# 28_main_board_vA.net
KiCad netlist of a schematic drawn in EAGLE
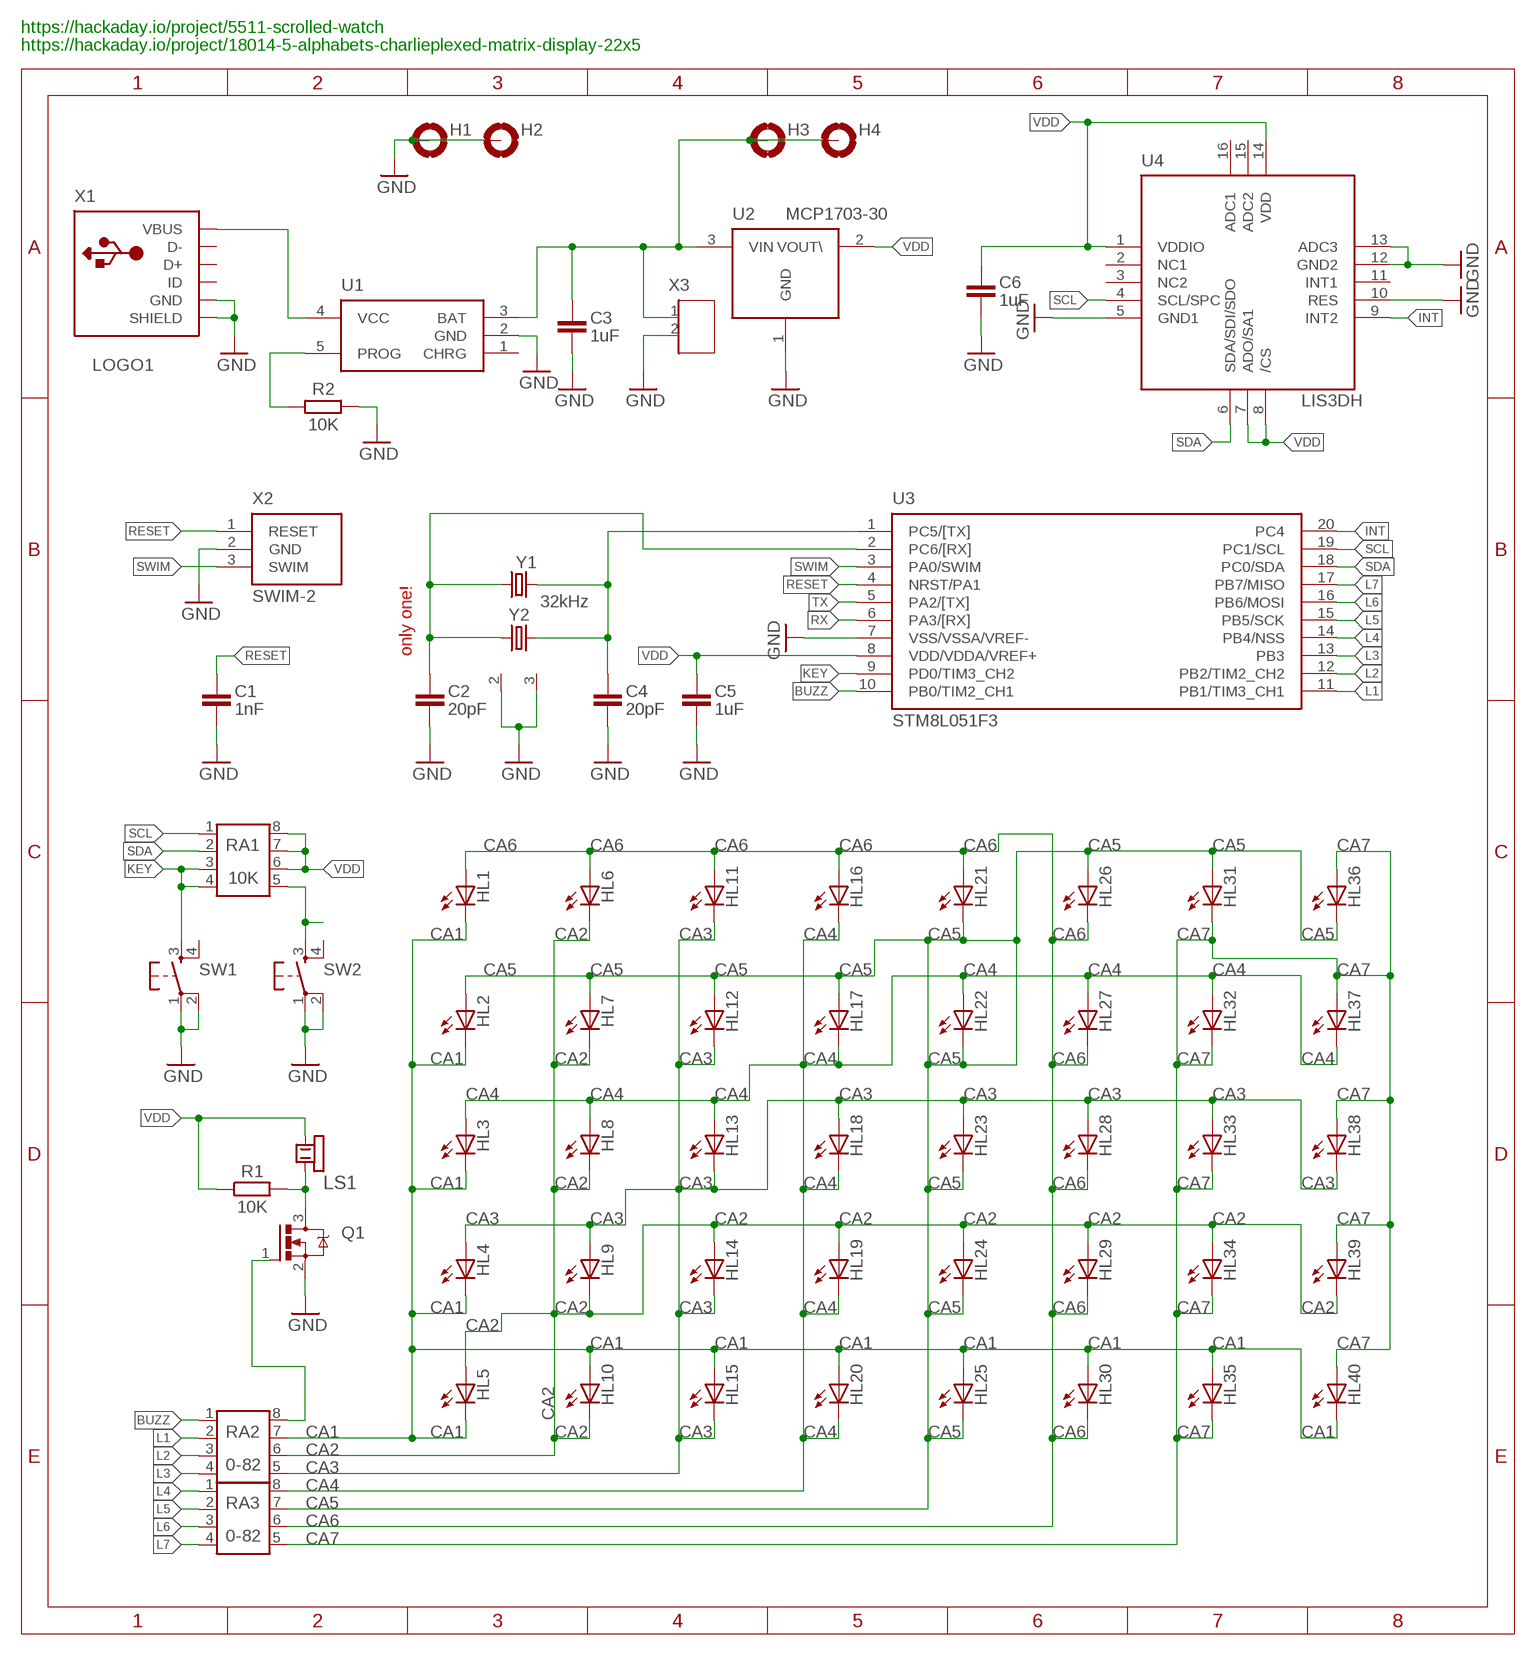
[diagram p0: schematic, sheet 1]

(export (version "E")
  (design (tool "Eeschema 10.0.6"))
  (components
    (comp (ref "C1")
      (value "1nF")
      (footprint "eagle-import:C0603")
      (libsource (lib "eagle-import") (part "C-EU-C0603"))
    )
    (comp (ref "C2")
      (value "20pF")
      (footprint "eagle-import:C0402")
      (libsource (lib "eagle-import") (part "C-EU-C0402"))
    )
    (comp (ref "C3")
      (value "1uF")
      (footprint "eagle-import:C0603")
      (libsource (lib "eagle-import") (part "C-EU-C0603"))
    )
    (comp (ref "C4")
      (value "20pF")
      (footprint "eagle-import:C0402")
      (libsource (lib "eagle-import") (part "C-EU-C0402"))
    )
    (comp (ref "C5")
      (value "1uF")
      (footprint "eagle-import:C0603")
      (libsource (lib "eagle-import") (part "C-EU-C0603"))
    )
    (comp (ref "C6")
      (value "1uF")
      (footprint "eagle-import:C0603")
      (libsource (lib "eagle-import") (part "C-EU-C0603"))
    )
    (comp (ref "H1")
      (value "MOUNT-PAD-ROUNDVA")
      (footprint "eagle-import:PAD-VA")
      (libsource (lib "eagle-import") (part "MOUNT-PAD-ROUNDVA"))
    )
    (comp (ref "H2")
      (value "MOUNT-PAD-ROUNDVA")
      (footprint "eagle-import:PAD-VA")
      (libsource (lib "eagle-import") (part "MOUNT-PAD-ROUNDVA"))
    )
    (comp (ref "H3")
      (value "MOUNT-PAD-ROUNDVA")
      (footprint "eagle-import:PAD-VA")
      (libsource (lib "eagle-import") (part "MOUNT-PAD-ROUNDVA"))
    )
    (comp (ref "H4")
      (value "MOUNT-PAD-ROUNDVA")
      (footprint "eagle-import:PAD-VA")
      (libsource (lib "eagle-import") (part "MOUNT-PAD-ROUNDVA"))
    )
    (comp (ref "HL1")
      (value "LED0603")
      (footprint "eagle-import:CHIPLED_0603")
      (libsource (lib "eagle-import") (part "LED0603"))
    )
    (comp (ref "HL2")
      (value "LED0603")
      (footprint "eagle-import:CHIPLED_0603")
      (libsource (lib "eagle-import") (part "LED0603"))
    )
    (comp (ref "HL3")
      (value "LED0603")
      (footprint "eagle-import:CHIPLED_0603")
      (libsource (lib "eagle-import") (part "LED0603"))
    )
    (comp (ref "HL4")
      (value "LED0603")
      (footprint "eagle-import:CHIPLED_0603")
      (libsource (lib "eagle-import") (part "LED0603"))
    )
    (comp (ref "HL5")
      (value "LED0603")
      (footprint "eagle-import:CHIPLED_0603")
      (libsource (lib "eagle-import") (part "LED0603"))
    )
    (comp (ref "HL6")
      (value "LED0603")
      (footprint "eagle-import:CHIPLED_0603")
      (libsource (lib "eagle-import") (part "LED0603"))
    )
    (comp (ref "HL7")
      (value "LED0603")
      (footprint "eagle-import:CHIPLED_0603")
      (libsource (lib "eagle-import") (part "LED0603"))
    )
    (comp (ref "HL8")
      (value "LED0603")
      (footprint "eagle-import:CHIPLED_0603")
      (libsource (lib "eagle-import") (part "LED0603"))
    )
    (comp (ref "HL9")
      (value "LED0603")
      (footprint "eagle-import:CHIPLED_0603")
      (libsource (lib "eagle-import") (part "LED0603"))
    )
    (comp (ref "HL10")
      (value "LED0603")
      (footprint "eagle-import:CHIPLED_0603")
      (libsource (lib "eagle-import") (part "LED0603"))
    )
    (comp (ref "HL11")
      (value "LED0603")
      (footprint "eagle-import:CHIPLED_0603")
      (libsource (lib "eagle-import") (part "LED0603"))
    )
    (comp (ref "HL12")
      (value "LED0603")
      (footprint "eagle-import:CHIPLED_0603")
      (libsource (lib "eagle-import") (part "LED0603"))
    )
    (comp (ref "HL13")
      (value "LED0603")
      (footprint "eagle-import:CHIPLED_0603")
      (libsource (lib "eagle-import") (part "LED0603"))
    )
    (comp (ref "HL14")
      (value "LED0603")
      (footprint "eagle-import:CHIPLED_0603")
      (libsource (lib "eagle-import") (part "LED0603"))
    )
    (comp (ref "HL15")
      (value "LED0603")
      (footprint "eagle-import:CHIPLED_0603")
      (libsource (lib "eagle-import") (part "LED0603"))
    )
    (comp (ref "HL16")
      (value "LED0603")
      (footprint "eagle-import:CHIPLED_0603")
      (libsource (lib "eagle-import") (part "LED0603"))
    )
    (comp (ref "HL17")
      (value "LED0603")
      (footprint "eagle-import:CHIPLED_0603")
      (libsource (lib "eagle-import") (part "LED0603"))
    )
    (comp (ref "HL18")
      (value "LED0603")
      (footprint "eagle-import:CHIPLED_0603")
      (libsource (lib "eagle-import") (part "LED0603"))
    )
    (comp (ref "HL19")
      (value "LED0603")
      (footprint "eagle-import:CHIPLED_0603")
      (libsource (lib "eagle-import") (part "LED0603"))
    )
    (comp (ref "HL20")
      (value "LED0603")
      (footprint "eagle-import:CHIPLED_0603")
      (libsource (lib "eagle-import") (part "LED0603"))
    )
    (comp (ref "HL21")
      (value "LED0603")
      (footprint "eagle-import:CHIPLED_0603")
      (libsource (lib "eagle-import") (part "LED0603"))
    )
    (comp (ref "HL22")
      (value "LED0603")
      (footprint "eagle-import:CHIPLED_0603")
      (libsource (lib "eagle-import") (part "LED0603"))
    )
    (comp (ref "HL23")
      (value "LED0603")
      (footprint "eagle-import:CHIPLED_0603")
      (libsource (lib "eagle-import") (part "LED0603"))
    )
    (comp (ref "HL24")
      (value "LED0603")
      (footprint "eagle-import:CHIPLED_0603")
      (libsource (lib "eagle-import") (part "LED0603"))
    )
    (comp (ref "HL25")
      (value "LED0603")
      (footprint "eagle-import:CHIPLED_0603")
      (libsource (lib "eagle-import") (part "LED0603"))
    )
    (comp (ref "HL26")
      (value "LED0603")
      (footprint "eagle-import:CHIPLED_0603")
      (libsource (lib "eagle-import") (part "LED0603"))
    )
    (comp (ref "HL27")
      (value "LED0603")
      (footprint "eagle-import:CHIPLED_0603")
      (libsource (lib "eagle-import") (part "LED0603"))
    )
    (comp (ref "HL28")
      (value "LED0603")
      (footprint "eagle-import:CHIPLED_0603")
      (libsource (lib "eagle-import") (part "LED0603"))
    )
    (comp (ref "HL29")
      (value "LED0603")
      (footprint "eagle-import:CHIPLED_0603")
      (libsource (lib "eagle-import") (part "LED0603"))
    )
    (comp (ref "HL30")
      (value "LED0603")
      (footprint "eagle-import:CHIPLED_0603")
      (libsource (lib "eagle-import") (part "LED0603"))
    )
    (comp (ref "HL31")
      (value "LED0603")
      (footprint "eagle-import:CHIPLED_0603")
      (libsource (lib "eagle-import") (part "LED0603"))
    )
    (comp (ref "HL32")
      (value "LED0603")
      (footprint "eagle-import:CHIPLED_0603")
      (libsource (lib "eagle-import") (part "LED0603"))
    )
    (comp (ref "HL33")
      (value "LED0603")
      (footprint "eagle-import:CHIPLED_0603")
      (libsource (lib "eagle-import") (part "LED0603"))
    )
    (comp (ref "HL34")
      (value "LED0603")
      (footprint "eagle-import:CHIPLED_0603")
      (libsource (lib "eagle-import") (part "LED0603"))
    )
    (comp (ref "HL35")
      (value "LED0603")
      (footprint "eagle-import:CHIPLED_0603")
      (libsource (lib "eagle-import") (part "LED0603"))
    )
    (comp (ref "HL36")
      (value "LED0603")
      (footprint "eagle-import:CHIPLED_0603")
      (libsource (lib "eagle-import") (part "LED0603"))
    )
    (comp (ref "HL37")
      (value "LED0603")
      (footprint "eagle-import:CHIPLED_0603")
      (libsource (lib "eagle-import") (part "LED0603"))
    )
    (comp (ref "HL38")
      (value "LED0603")
      (footprint "eagle-import:CHIPLED_0603")
      (libsource (lib "eagle-import") (part "LED0603"))
    )
    (comp (ref "HL39")
      (value "LED0603")
      (footprint "eagle-import:CHIPLED_0603")
      (libsource (lib "eagle-import") (part "LED0603"))
    )
    (comp (ref "HL40")
      (value "LED0603")
      (footprint "eagle-import:CHIPLED_0603")
      (libsource (lib "eagle-import") (part "LED0603"))
    )
    (comp (ref "LOGO1")
      (value "LOGO-7")
      (footprint "eagle-import:LOGO_OMEGA_COPPER")
      (libsource (lib "eagle-import") (part "LOGO-7"))
    )
    (comp (ref "LS1")
      (value "BUZZER-PIEZO")
      (footprint "eagle-import:BUZZER-PCB-PAD-VA")
      (libsource (lib "eagle-import") (part "BUZZER-PIEZO"))
    )
    (comp (ref "Q1")
      (value "FET_NSOT23")
      (footprint "eagle-import:SOT23-3-1")
      (libsource (lib "eagle-import") (part "FET_NSOT23"))
    )
    (comp (ref "R1")
      (value "10K")
      (footprint "eagle-import:R0603")
      (libsource (lib "eagle-import") (part "R-EU0603"))
    )
    (comp (ref "R2")
      (value "10K")
      (footprint "eagle-import:R0402")
      (libsource (lib "eagle-import") (part "R-EU0402"))
    )
    (comp (ref "RA1")
      (value "10K")
      (footprint "eagle-import:EXB38V")
      (libsource (lib "eagle-import") (part "R-ARRAY-4X0603"))
    )
    (comp (ref "RA2")
      (value "0-82")
      (footprint "eagle-import:EXB38V")
      (libsource (lib "eagle-import") (part "R-ARRAY-4X0603"))
    )
    (comp (ref "RA3")
      (value "0-82")
      (footprint "eagle-import:EXB38V")
      (libsource (lib "eagle-import") (part "R-ARRAY-4X0603"))
    )
    (comp (ref "SW1")
      (value "SWITCH_G2SM")
      (footprint "eagle-import:SW_TACT_SMALL")
      (libsource (lib "eagle-import") (part "SWITCH_G2SM"))
    )
    (comp (ref "SW2")
      (value "SWITCH_G2SM")
      (footprint "eagle-import:SW_TACT_SMALL")
      (libsource (lib "eagle-import") (part "SWITCH_G2SM"))
    )
    (comp (ref "U1")
      (value "LTC4054")
      (footprint "eagle-import:SOT23-5L")
      (libsource (lib "eagle-import") (part "LTC4054"))
    )
    (comp (ref "U2")
      (value "MCP1703-30")
      (footprint "eagle-import:SOT23-3")
      (libsource (lib "eagle-import") (part "MCP170XSOT23"))
    )
    (comp (ref "U3")
      (value "STM8L051F3")
      (footprint "eagle-import:TSSOP20")
      (libsource (lib "eagle-import") (part "STM8L051F3"))
    )
    (comp (ref "U4")
      (value "LIS3DH")
      (footprint "eagle-import:LGA16")
      (libsource (lib "eagle-import") (part "LIS3DH"))
    )
    (comp (ref "X1")
      (value "USB-5S-MICRO")
      (footprint "eagle-import:USB-B-MICRO-SMD_V03")
      (libsource (lib "eagle-import") (part "USB-5S-MICRO"))
    )
    (comp (ref "X2")
      (value "SWIM-2")
      (footprint "eagle-import:ISP-TYPEB-3")
      (libsource (lib "eagle-import") (part "SWIM-2"))
    )
    (comp (ref "X3")
      (value "CON-2P-1")
      (footprint "eagle-import:PLS-2.54-2")
      (libsource (lib "eagle-import") (part "CON-2P-1"))
    )
    (comp (ref "Y1")
      (value "32kHz")
      (footprint "eagle-import:XTAL3215")
      (libsource (lib "eagle-import") (part "REZONATOR-2PIN3215"))
    )
    (comp (ref "Y2")
      (value "REZONATOR-4PIN-SJK-7M")
      (footprint "eagle-import:SJK-7M")
      (libsource (lib "eagle-import") (part "REZONATOR-4PIN-SJK-7M"))
    )
  )
  (nets
    (net (code "1") (name "/CA1") (class "Default")
      (node (ref "HL1") (pin "C") (pinfunction "C_C") (pintype "passive"))
      (node (ref "HL10") (pin "A") (pinfunction "A_A") (pintype "passive"))
      (node (ref "HL15") (pin "A") (pinfunction "A_A") (pintype "passive"))
      (node (ref "HL2") (pin "C") (pinfunction "C_C") (pintype "passive"))
      (node (ref "HL20") (pin "A") (pinfunction "A_A") (pintype "passive"))
      (node (ref "HL25") (pin "A") (pinfunction "A_A") (pintype "passive"))
      (node (ref "HL3") (pin "C") (pinfunction "C_C") (pintype "passive"))
      (node (ref "HL30") (pin "A") (pinfunction "A_A") (pintype "passive"))
      (node (ref "HL35") (pin "A") (pinfunction "A_A") (pintype "passive"))
      (node (ref "HL4") (pin "C") (pinfunction "C_C") (pintype "passive"))
      (node (ref "HL40") (pin "C") (pinfunction "C_C") (pintype "passive"))
      (node (ref "HL5") (pin "C") (pinfunction "C_C") (pintype "passive"))
      (node (ref "RA2") (pin "7") (pinfunction "7_7") (pintype "passive"))
    )
    (net (code "2") (name "/CA2") (class "Default")
      (node (ref "HL10") (pin "C") (pinfunction "C_C") (pintype "passive"))
      (node (ref "HL14") (pin "A") (pinfunction "A_A") (pintype "passive"))
      (node (ref "HL19") (pin "A") (pinfunction "A_A") (pintype "passive"))
      (node (ref "HL24") (pin "A") (pinfunction "A_A") (pintype "passive"))
      (node (ref "HL29") (pin "A") (pinfunction "A_A") (pintype "passive"))
      (node (ref "HL34") (pin "A") (pinfunction "A_A") (pintype "passive"))
      (node (ref "HL39") (pin "C") (pinfunction "C_C") (pintype "passive"))
      (node (ref "HL5") (pin "A") (pinfunction "A_A") (pintype "passive"))
      (node (ref "HL6") (pin "C") (pinfunction "C_C") (pintype "passive"))
      (node (ref "HL7") (pin "C") (pinfunction "C_C") (pintype "passive"))
      (node (ref "HL8") (pin "C") (pinfunction "C_C") (pintype "passive"))
      (node (ref "HL9") (pin "C") (pinfunction "C_C") (pintype "passive"))
      (node (ref "RA2") (pin "6") (pinfunction "6_6") (pintype "passive"))
    )
    (net (code "3") (name "/CA3") (class "Default")
      (node (ref "HL11") (pin "C") (pinfunction "C_C") (pintype "passive"))
      (node (ref "HL12") (pin "C") (pinfunction "C_C") (pintype "passive"))
      (node (ref "HL13") (pin "C") (pinfunction "C_C") (pintype "passive"))
      (node (ref "HL14") (pin "C") (pinfunction "C_C") (pintype "passive"))
      (node (ref "HL15") (pin "C") (pinfunction "C_C") (pintype "passive"))
      (node (ref "HL18") (pin "A") (pinfunction "A_A") (pintype "passive"))
      (node (ref "HL23") (pin "A") (pinfunction "A_A") (pintype "passive"))
      (node (ref "HL28") (pin "A") (pinfunction "A_A") (pintype "passive"))
      (node (ref "HL33") (pin "A") (pinfunction "A_A") (pintype "passive"))
      (node (ref "HL38") (pin "C") (pinfunction "C_C") (pintype "passive"))
      (node (ref "HL4") (pin "A") (pinfunction "A_A") (pintype "passive"))
      (node (ref "HL9") (pin "A") (pinfunction "A_A") (pintype "passive"))
      (node (ref "RA2") (pin "5") (pinfunction "5_5") (pintype "passive"))
    )
    (net (code "4") (name "/CA4") (class "Default")
      (node (ref "HL13") (pin "A") (pinfunction "A_A") (pintype "passive"))
      (node (ref "HL16") (pin "C") (pinfunction "C_C") (pintype "passive"))
      (node (ref "HL17") (pin "C") (pinfunction "C_C") (pintype "passive"))
      (node (ref "HL18") (pin "C") (pinfunction "C_C") (pintype "passive"))
      (node (ref "HL19") (pin "C") (pinfunction "C_C") (pintype "passive"))
      (node (ref "HL20") (pin "C") (pinfunction "C_C") (pintype "passive"))
      (node (ref "HL22") (pin "A") (pinfunction "A_A") (pintype "passive"))
      (node (ref "HL27") (pin "A") (pinfunction "A_A") (pintype "passive"))
      (node (ref "HL3") (pin "A") (pinfunction "A_A") (pintype "passive"))
      (node (ref "HL32") (pin "A") (pinfunction "A_A") (pintype "passive"))
      (node (ref "HL37") (pin "C") (pinfunction "C_C") (pintype "passive"))
      (node (ref "HL8") (pin "A") (pinfunction "A_A") (pintype "passive"))
      (node (ref "RA3") (pin "8") (pinfunction "8_8") (pintype "passive"))
    )
    (net (code "5") (name "/CA5") (class "Default")
      (node (ref "HL12") (pin "A") (pinfunction "A_A") (pintype "passive"))
      (node (ref "HL17") (pin "A") (pinfunction "A_A") (pintype "passive"))
      (node (ref "HL2") (pin "A") (pinfunction "A_A") (pintype "passive"))
      (node (ref "HL21") (pin "C") (pinfunction "C_C") (pintype "passive"))
      (node (ref "HL22") (pin "C") (pinfunction "C_C") (pintype "passive"))
      (node (ref "HL23") (pin "C") (pinfunction "C_C") (pintype "passive"))
      (node (ref "HL24") (pin "C") (pinfunction "C_C") (pintype "passive"))
      (node (ref "HL25") (pin "C") (pinfunction "C_C") (pintype "passive"))
      (node (ref "HL26") (pin "A") (pinfunction "A_A") (pintype "passive"))
      (node (ref "HL31") (pin "A") (pinfunction "A_A") (pintype "passive"))
      (node (ref "HL36") (pin "C") (pinfunction "C_C") (pintype "passive"))
      (node (ref "HL7") (pin "A") (pinfunction "A_A") (pintype "passive"))
      (node (ref "RA3") (pin "7") (pinfunction "7_7") (pintype "passive"))
    )
    (net (code "6") (name "/CA6") (class "Default")
      (node (ref "HL1") (pin "A") (pinfunction "A_A") (pintype "passive"))
      (node (ref "HL11") (pin "A") (pinfunction "A_A") (pintype "passive"))
      (node (ref "HL16") (pin "A") (pinfunction "A_A") (pintype "passive"))
      (node (ref "HL21") (pin "A") (pinfunction "A_A") (pintype "passive"))
      (node (ref "HL26") (pin "C") (pinfunction "C_C") (pintype "passive"))
      (node (ref "HL27") (pin "C") (pinfunction "C_C") (pintype "passive"))
      (node (ref "HL28") (pin "C") (pinfunction "C_C") (pintype "passive"))
      (node (ref "HL29") (pin "C") (pinfunction "C_C") (pintype "passive"))
      (node (ref "HL30") (pin "C") (pinfunction "C_C") (pintype "passive"))
      (node (ref "HL6") (pin "A") (pinfunction "A_A") (pintype "passive"))
      (node (ref "RA3") (pin "6") (pinfunction "6_6") (pintype "passive"))
    )
    (net (code "7") (name "/CA7") (class "Default")
      (node (ref "HL31") (pin "C") (pinfunction "C_C") (pintype "passive"))
      (node (ref "HL32") (pin "C") (pinfunction "C_C") (pintype "passive"))
      (node (ref "HL33") (pin "C") (pinfunction "C_C") (pintype "passive"))
      (node (ref "HL34") (pin "C") (pinfunction "C_C") (pintype "passive"))
      (node (ref "HL35") (pin "C") (pinfunction "C_C") (pintype "passive"))
      (node (ref "HL36") (pin "A") (pinfunction "A_A") (pintype "passive"))
      (node (ref "HL37") (pin "A") (pinfunction "A_A") (pintype "passive"))
      (node (ref "HL38") (pin "A") (pinfunction "A_A") (pintype "passive"))
      (node (ref "HL39") (pin "A") (pinfunction "A_A") (pintype "passive"))
      (node (ref "HL40") (pin "A") (pinfunction "A_A") (pintype "passive"))
      (node (ref "RA3") (pin "5") (pinfunction "5_5") (pintype "passive"))
    )
    (net (code "8") (name "BUZZ") (class "Default")
      (node (ref "RA2") (pin "1") (pinfunction "1_1") (pintype "passive"))
      (node (ref "U3") (pin "10") (pinfunction "PB0/TIM2_CH1_10") (pintype "bidirectional"))
    )
    (net (code "9") (name "GND") (class "Default")
      (node (ref "C1") (pin "2") (pinfunction "2_2") (pintype "passive"))
      (node (ref "C2") (pin "2") (pinfunction "2_2") (pintype "passive"))
      (node (ref "C3") (pin "2") (pinfunction "2_2") (pintype "passive"))
      (node (ref "C4") (pin "2") (pinfunction "2_2") (pintype "passive"))
      (node (ref "C5") (pin "2") (pinfunction "2_2") (pintype "passive"))
      (node (ref "C6") (pin "2") (pinfunction "2_2") (pintype "passive"))
      (node (ref "H1") (pin "1") (pinfunction "MOUNT_1") (pintype "passive"))
      (node (ref "H2") (pin "1") (pinfunction "MOUNT_1") (pintype "passive"))
      (node (ref "Q1") (pin "2") (pinfunction "S_2") (pintype "passive"))
      (node (ref "R2") (pin "1") (pinfunction "1_1") (pintype "passive"))
      (node (ref "SW1") (pin "1") (pinfunction "P_1") (pintype "passive"))
      (node (ref "SW1") (pin "2") (pinfunction "P1_2") (pintype "passive"))
      (node (ref "SW2") (pin "1") (pinfunction "P_1") (pintype "passive"))
      (node (ref "SW2") (pin "2") (pinfunction "P1_2") (pintype "passive"))
      (node (ref "U1") (pin "2") (pinfunction "GND_2") (pintype "bidirectional"))
      (node (ref "U2") (pin "1") (pinfunction "GND_1") (pintype "bidirectional"))
      (node (ref "U3") (pin "7") (pinfunction "VSS/VSSA/VREF-_7") (pintype "bidirectional"))
      (node (ref "U4") (pin "10") (pinfunction "RES_10") (pintype "bidirectional"))
      (node (ref "U4") (pin "12") (pinfunction "GND2_12") (pintype "bidirectional"))
      (node (ref "U4") (pin "13") (pinfunction "ADC3_13") (pintype "bidirectional"))
      (node (ref "U4") (pin "5") (pinfunction "GND1_5") (pintype "bidirectional"))
      (node (ref "X1") (pin "GND1") (pinfunction "GND_GND1") (pintype "power_in"))
      (node (ref "X1") (pin "SHIELD@1") (pinfunction "SHIELD_SHIELD@1") (pintype "bidirectional"))
      (node (ref "X1") (pin "SHIELD@2") (pinfunction "SHIELD_SHIELD@2") (pintype "bidirectional"))
      (node (ref "X1") (pin "SHIELD@3") (pinfunction "SHIELD_SHIELD@3") (pintype "bidirectional"))
      (node (ref "X1") (pin "SHIELD@4") (pinfunction "SHIELD_SHIELD@4") (pintype "bidirectional"))
      (node (ref "X1") (pin "SHIELD@5") (pinfunction "SHIELD_SHIELD@5") (pintype "bidirectional"))
      (node (ref "X2") (pin "2") (pinfunction "GND_2") (pintype "bidirectional"))
      (node (ref "X3") (pin "2") (pinfunction "2_2") (pintype "bidirectional"))
      (node (ref "Y2") (pin "2") (pinfunction "S_2") (pintype "bidirectional"))
      (node (ref "Y2") (pin "3") (pinfunction "S_3") (pintype "bidirectional"))
    )
    (net (code "10") (name "INT") (class "Default")
      (node (ref "U3") (pin "20") (pinfunction "PC4_20") (pintype "bidirectional"))
      (node (ref "U4") (pin "9") (pinfunction "INT2_9") (pintype "bidirectional"))
    )
    (net (code "11") (name "KEY") (class "Default")
      (node (ref "RA1") (pin "3") (pinfunction "3_3") (pintype "passive"))
      (node (ref "RA1") (pin "4") (pinfunction "4_4") (pintype "passive"))
      (node (ref "SW1") (pin "3") (pinfunction "S_3") (pintype "passive"))
      (node (ref "U3") (pin "9") (pinfunction "PD0/TIM3_CH2_9") (pintype "bidirectional"))
    )
    (net (code "12") (name "L1") (class "Default")
      (node (ref "RA2") (pin "2") (pinfunction "2_2") (pintype "passive"))
      (node (ref "U3") (pin "11") (pinfunction "PB1/TIM3_CH1_11") (pintype "bidirectional"))
    )
    (net (code "13") (name "L2") (class "Default")
      (node (ref "RA2") (pin "3") (pinfunction "3_3") (pintype "passive"))
      (node (ref "U3") (pin "12") (pinfunction "PB2/TIM2_CH2_12") (pintype "bidirectional"))
    )
    (net (code "14") (name "L3") (class "Default")
      (node (ref "RA2") (pin "4") (pinfunction "4_4") (pintype "passive"))
      (node (ref "U3") (pin "13") (pinfunction "PB3_13") (pintype "bidirectional"))
    )
    (net (code "15") (name "L4") (class "Default")
      (node (ref "RA3") (pin "1") (pinfunction "1_1") (pintype "passive"))
      (node (ref "U3") (pin "14") (pinfunction "PB4/NSS_14") (pintype "bidirectional"))
    )
    (net (code "16") (name "L5") (class "Default")
      (node (ref "RA3") (pin "2") (pinfunction "2_2") (pintype "passive"))
      (node (ref "U3") (pin "15") (pinfunction "PB5/SCK_15") (pintype "bidirectional"))
    )
    (net (code "17") (name "L6") (class "Default")
      (node (ref "RA3") (pin "3") (pinfunction "3_3") (pintype "passive"))
      (node (ref "U3") (pin "16") (pinfunction "PB6/MOSI_16") (pintype "bidirectional"))
    )
    (net (code "18") (name "L7") (class "Default")
      (node (ref "RA3") (pin "4") (pinfunction "4_4") (pintype "passive"))
      (node (ref "U3") (pin "17") (pinfunction "PB7/MISO_17") (pintype "bidirectional"))
    )
    (net (code "19") (name "Net-(H3-MOUNT)") (class "Default")
      (node (ref "C3") (pin "1") (pinfunction "1_1") (pintype "passive"))
      (node (ref "H3") (pin "1") (pinfunction "MOUNT_1") (pintype "passive"))
      (node (ref "H4") (pin "1") (pinfunction "MOUNT_1") (pintype "passive"))
      (node (ref "U1") (pin "3") (pinfunction "BAT_3") (pintype "bidirectional"))
      (node (ref "U2") (pin "3") (pinfunction "VIN_3") (pintype "bidirectional"))
      (node (ref "X3") (pin "1") (pinfunction "1_1") (pintype "bidirectional"))
    )
    (net (code "20") (name "Net-(Q1-D)") (class "Default")
      (node (ref "LS1") (pin "2") (pinfunction "2_2") (pintype "passive"))
      (node (ref "Q1") (pin "3") (pinfunction "D_3") (pintype "passive"))
      (node (ref "R1") (pin "2") (pinfunction "2_2") (pintype "passive"))
    )
    (net (code "21") (name "Net-(Q1-G)") (class "Default")
      (node (ref "Q1") (pin "1") (pinfunction "G_1") (pintype "passive"))
      (node (ref "RA2") (pin "8") (pinfunction "8_8") (pintype "passive"))
    )
    (net (code "22") (name "Net-(SW2-S)") (class "Default")
      (node (ref "RA1") (pin "5") (pinfunction "5_5") (pintype "passive"))
      (node (ref "SW2") (pin "3") (pinfunction "S_3") (pintype "passive"))
    )
    (net (code "23") (name "Net-(U1-PROG)") (class "Default")
      (node (ref "R2") (pin "2") (pinfunction "2_2") (pintype "passive"))
      (node (ref "U1") (pin "5") (pinfunction "PROG_5") (pintype "bidirectional"))
    )
    (net (code "24") (name "Net-(U1-VCC)") (class "Default")
      (node (ref "U1") (pin "4") (pinfunction "VCC_4") (pintype "bidirectional"))
      (node (ref "X1") (pin "VBUS1") (pinfunction "VBUS_VBUS1") (pintype "bidirectional"))
    )
    (net (code "25") (name "Net-(U3-PC5{slash}[TX])") (class "Default")
      (node (ref "C4") (pin "1") (pinfunction "1_1") (pintype "passive"))
      (node (ref "U3") (pin "1") (pinfunction "PC5/[TX]_1") (pintype "bidirectional"))
      (node (ref "Y1") (pin "1") (pinfunction "1_1") (pintype "passive"))
      (node (ref "Y2") (pin "4") (pinfunction "2_4") (pintype "passive"))
    )
    (net (code "26") (name "Net-(U3-PC6{slash}[RX])") (class "Default")
      (node (ref "C2") (pin "1") (pinfunction "1_1") (pintype "passive"))
      (node (ref "U3") (pin "2") (pinfunction "PC6/[RX]_2") (pintype "bidirectional"))
      (node (ref "Y1") (pin "2") (pinfunction "2_2") (pintype "passive"))
      (node (ref "Y2") (pin "1") (pinfunction "1_1") (pintype "passive"))
    )
    (net (code "27") (name "RESET") (class "Default")
      (node (ref "C1") (pin "1") (pinfunction "1_1") (pintype "passive"))
      (node (ref "U3") (pin "4") (pinfunction "NRST/PA1_4") (pintype "bidirectional"))
      (node (ref "X2") (pin "1") (pinfunction "RESET_1") (pintype "bidirectional"))
    )
    (net (code "28") (name "RX") (class "Default")
      (node (ref "U3") (pin "6") (pinfunction "PA3/[RX]_6") (pintype "bidirectional"))
    )
    (net (code "29") (name "SCL") (class "Default")
      (node (ref "RA1") (pin "1") (pinfunction "1_1") (pintype "passive"))
      (node (ref "U3") (pin "19") (pinfunction "PC1/SCL_19") (pintype "bidirectional"))
      (node (ref "U4") (pin "4") (pinfunction "SCL/SPC_4") (pintype "bidirectional"))
    )
    (net (code "30") (name "SDA") (class "Default")
      (node (ref "RA1") (pin "2") (pinfunction "2_2") (pintype "passive"))
      (node (ref "U3") (pin "18") (pinfunction "PC0/SDA_18") (pintype "bidirectional"))
      (node (ref "U4") (pin "6") (pinfunction "SDA/SDI/SDO_6") (pintype "bidirectional"))
    )
    (net (code "31") (name "SWIM") (class "Default")
      (node (ref "U3") (pin "3") (pinfunction "PA0/SWIM_3") (pintype "bidirectional"))
      (node (ref "X2") (pin "3") (pinfunction "SWIM_3") (pintype "bidirectional"))
    )
    (net (code "32") (name "TX") (class "Default")
      (node (ref "U3") (pin "5") (pinfunction "PA2/[TX]_5") (pintype "bidirectional"))
    )
    (net (code "33") (name "VDD") (class "Default")
      (node (ref "C5") (pin "1") (pinfunction "1_1") (pintype "passive"))
      (node (ref "C6") (pin "1") (pinfunction "1_1") (pintype "passive"))
      (node (ref "LS1") (pin "1") (pinfunction "1_1") (pintype "passive"))
      (node (ref "R1") (pin "1") (pinfunction "1_1") (pintype "passive"))
      (node (ref "RA1") (pin "6") (pinfunction "6_6") (pintype "passive"))
      (node (ref "RA1") (pin "7") (pinfunction "7_7") (pintype "passive"))
      (node (ref "RA1") (pin "8") (pinfunction "8_8") (pintype "passive"))
      (node (ref "U2") (pin "2") (pinfunction "VOUT\\_2") (pintype "bidirectional"))
      (node (ref "U3") (pin "8") (pinfunction "VDD/VDDA/VREF+_8") (pintype "bidirectional"))
      (node (ref "U4") (pin "1") (pinfunction "VDDIO_1") (pintype "bidirectional"))
      (node (ref "U4") (pin "14") (pinfunction "VDD_14") (pintype "bidirectional"))
      (node (ref "U4") (pin "7") (pinfunction "ADO/SA1_7") (pintype "bidirectional"))
      (node (ref "U4") (pin "8") (pinfunction "/CS_8") (pintype "bidirectional"))
    )
    (net (code "34") (name "unconnected-(SW1-S1-Pad4)") (class "Default")
      (node (ref "SW1") (pin "4") (pinfunction "S1_4") (pintype "passive"))
    )
    (net (code "35") (name "unconnected-(SW2-S1-Pad4)") (class "Default")
      (node (ref "SW2") (pin "4") (pinfunction "S1_4") (pintype "passive"))
    )
    (net (code "36") (name "unconnected-(U1-CHRG-Pad1)") (class "Default")
      (node (ref "U1") (pin "1") (pinfunction "CHRG_1") (pintype "bidirectional"))
    )
    (net (code "37") (name "unconnected-(U4-ADC1-Pad16)") (class "Default")
      (node (ref "U4") (pin "16") (pinfunction "ADC1_16") (pintype "bidirectional"))
    )
    (net (code "38") (name "unconnected-(U4-ADC2-Pad15)") (class "Default")
      (node (ref "U4") (pin "15") (pinfunction "ADC2_15") (pintype "bidirectional"))
    )
    (net (code "39") (name "unconnected-(U4-INT1-Pad11)") (class "Default")
      (node (ref "U4") (pin "11") (pinfunction "INT1_11") (pintype "bidirectional"))
    )
    (net (code "40") (name "unconnected-(U4-NC1-Pad2)") (class "Default")
      (node (ref "U4") (pin "2") (pinfunction "NC1_2") (pintype "bidirectional"))
    )
    (net (code "41") (name "unconnected-(U4-NC2-Pad3)") (class "Default")
      (node (ref "U4") (pin "3") (pinfunction "NC2_3") (pintype "bidirectional"))
    )
    (net (code "42") (name "unconnected-(X1-D+-PadD+1)") (class "Default")
      (node (ref "X1") (pin "D+1") (pinfunction "D+_D+1") (pintype "bidirectional"))
    )
    (net (code "43") (name "unconnected-(X1-D--PadD-1)") (class "Default")
      (node (ref "X1") (pin "D-1") (pinfunction "D-_D-1") (pintype "bidirectional"))
    )
    (net (code "44") (name "unconnected-(X1-ID-PadID1)") (class "Default")
      (node (ref "X1") (pin "ID1") (pinfunction "ID_ID1") (pintype "bidirectional"))
    )
  )
)
